# star.net
KiCad netlist of a schematic drawn in EAGLE
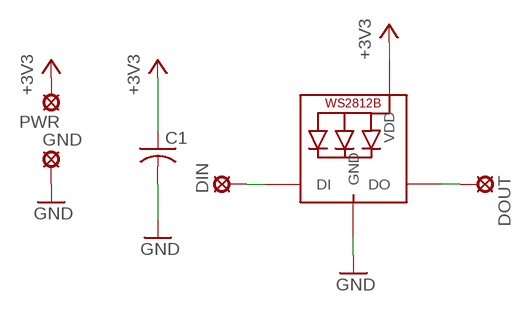
[diagram p0: schematic, sheet 1]

(export (version "E")
  (design (tool "Eeschema 10.0.6"))
  (components
    (comp (ref "C1")
      (value "C-USC0402K")
      (footprint "eagle-import:C0402K")
      (libsource (lib "eagle-import") (part "C-USC0402K"))
    )
    (comp (ref "DIN")
      (value "50THOU")
      (footprint "eagle-import:50THOU")
      (libsource (lib "eagle-import") (part "50THOU"))
    )
    (comp (ref "DOUT")
      (value "50THOU")
      (footprint "eagle-import:50THOU")
      (libsource (lib "eagle-import") (part "50THOU"))
    )
    (comp (ref "GND")
      (value "50THOU")
      (footprint "eagle-import:50THOU")
      (libsource (lib "eagle-import") (part "50THOU"))
    )
    (comp (ref "LED1")
      (value "WS2812B5050")
      (footprint "eagle-import:WS2812B")
      (libsource (lib "eagle-import") (part "WS2812B5050"))
    )
    (comp (ref "PWR")
      (value "50THOU")
      (footprint "eagle-import:50THOU")
      (libsource (lib "eagle-import") (part "50THOU"))
    )
  )
  (nets
    (net (code "1") (name "+3V3") (class "Default")
      (node (ref "C1") (pin "1") (pinfunction "1_1") (pintype "passive"))
      (node (ref "LED1") (pin "1-VDD") (pinfunction "VDD_1-VDD") (pintype "power_in"))
      (node (ref "PWR") (pin "P$1") (pinfunction "MP_P$1") (pintype "passive"))
    )
    (net (code "2") (name "GND") (class "Default")
      (node (ref "C1") (pin "2") (pinfunction "2_2") (pintype "passive"))
      (node (ref "GND") (pin "P$1") (pinfunction "MP_P$1") (pintype "passive"))
      (node (ref "LED1") (pin "3-GND") (pinfunction "GND_3-GND") (pintype "power_in"))
    )
    (net (code "3") (name "Net-(DIN-MP)") (class "Default")
      (node (ref "DIN") (pin "P$1") (pinfunction "MP_P$1") (pintype "passive"))
      (node (ref "LED1") (pin "4-DIN") (pinfunction "DI_4-DIN") (pintype "input"))
    )
    (net (code "4") (name "Net-(DOUT-MP)") (class "Default")
      (node (ref "DOUT") (pin "P$1") (pinfunction "MP_P$1") (pintype "passive"))
      (node (ref "LED1") (pin "2-DOUT") (pinfunction "DO_2-DOUT") (pintype "output"))
    )
  )
)
